# Microcontroller.net
KiCad netlist of a schematic drawn in Altium Designer
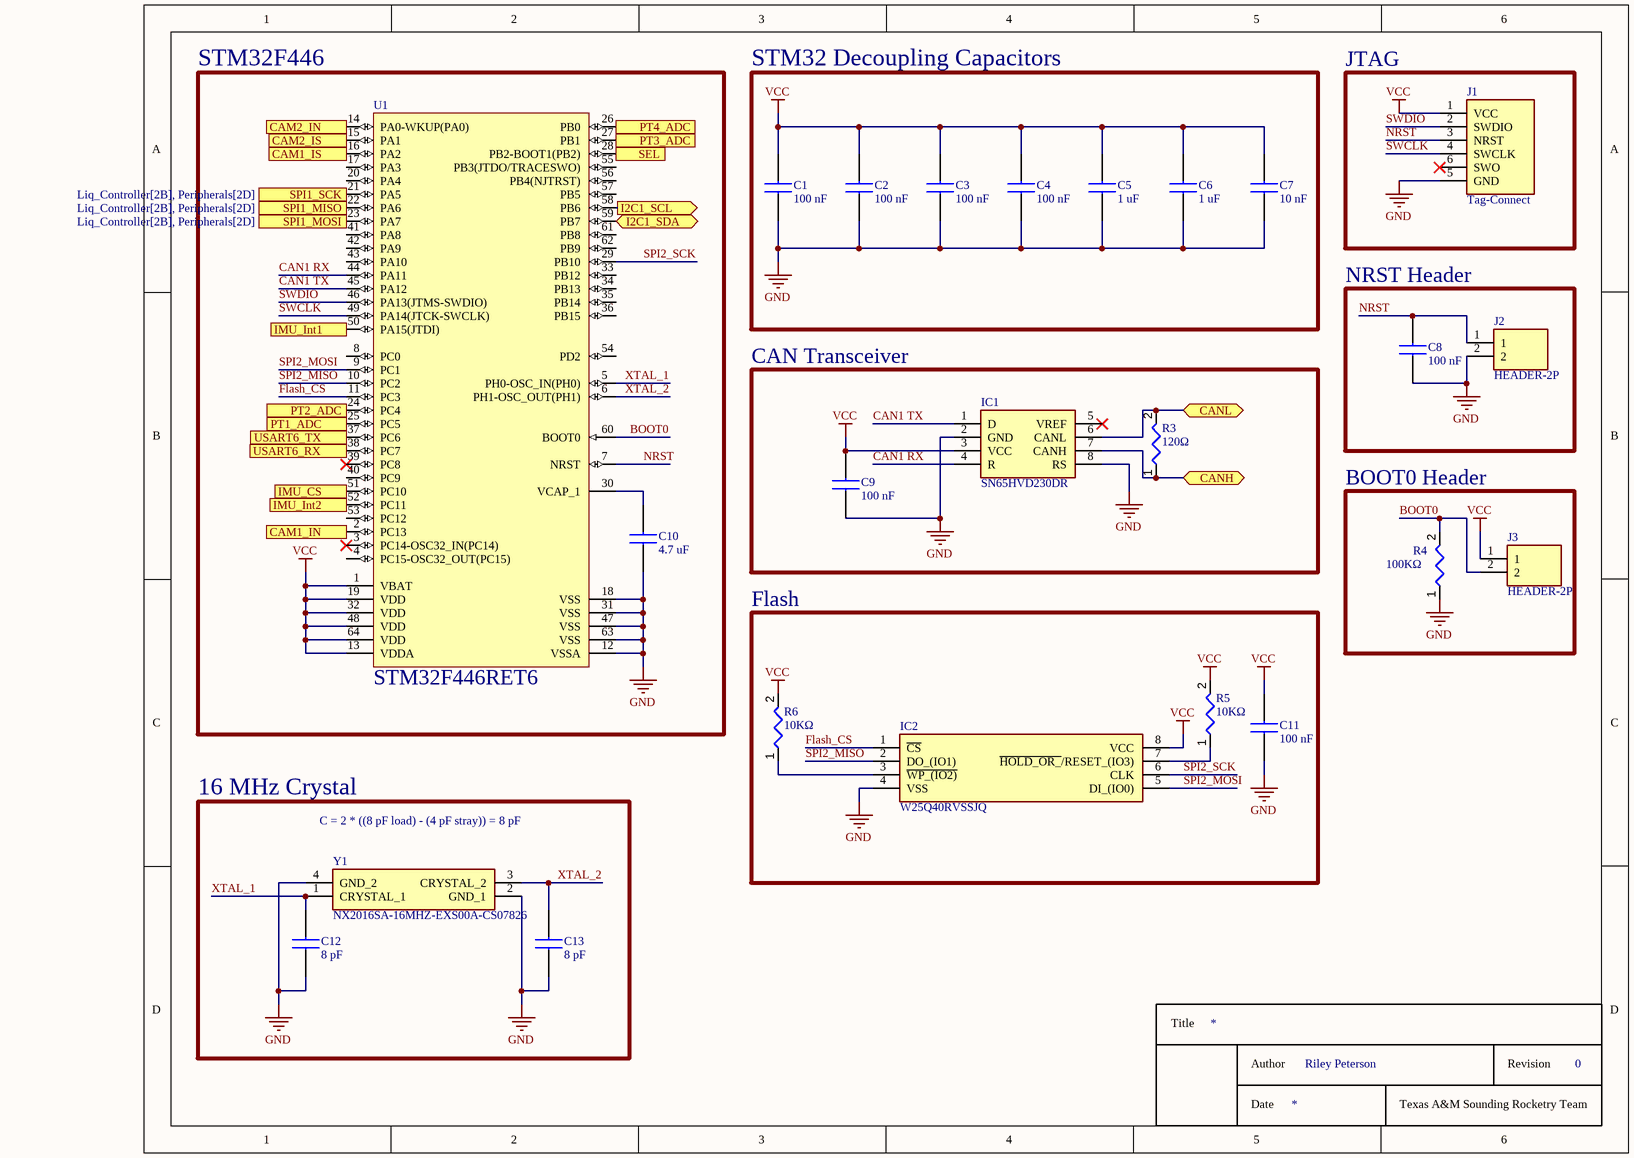
[diagram p0: Microcontroller.SchDoc]

(export (version "E")
  (design (tool "Eeschema 10.0.6"))
  (components
    (comp (ref "C1")
      (value "100 nF")
      (footprint "CAP_0603")
      (fields (field (name "TOLERANCE") "5%") (field (name "VOLTAGE") "50 V"))
      (libsource (lib "Capacitors") (part "Capacitor_BASE"))
    )
    (comp (ref "C2")
      (value "100 nF")
      (footprint "CAP_0603")
      (fields (field (name "TOLERANCE") "5%") (field (name "VOLTAGE") "50 V"))
      (libsource (lib "Capacitors") (part "Capacitor_BASE"))
    )
    (comp (ref "C3")
      (value "100 nF")
      (footprint "CAP_0603")
      (fields (field (name "TOLERANCE") "5%") (field (name "VOLTAGE") "50 V"))
      (libsource (lib "Capacitors") (part "Capacitor_BASE"))
    )
    (comp (ref "C4")
      (value "100 nF")
      (footprint "CAP_0603")
      (fields (field (name "TOLERANCE") "5%") (field (name "VOLTAGE") "50 V"))
      (libsource (lib "Capacitors") (part "Capacitor_BASE"))
    )
    (comp (ref "C5")
      (value "1 uF")
      (footprint "CAP_0603")
      (fields (field (name "TOLERANCE") "10%") (field (name "VOLTAGE") "25 V"))
      (libsource (lib "Capacitors") (part "Capacitor_BASE"))
    )
    (comp (ref "C6")
      (value "1 uF")
      (footprint "CAP_0603")
      (fields (field (name "TOLERANCE") "10%") (field (name "VOLTAGE") "25 V"))
      (libsource (lib "Capacitors") (part "Capacitor_BASE"))
    )
    (comp (ref "C7")
      (value "10 nF")
      (footprint "CAP_0603")
      (fields (field (name "TOLERANCE") "5%") (field (name "VOLTAGE") "50 V"))
      (libsource (lib "Capacitors") (part "Capacitor_BASE"))
    )
    (comp (ref "C8")
      (value "100 nF")
      (footprint "CAP_0603")
      (fields (field (name "TOLERANCE") "5%") (field (name "VOLTAGE") "50 V"))
      (libsource (lib "Capacitors") (part "Capacitor_BASE"))
    )
    (comp (ref "C9")
      (value "100 nF")
      (footprint "CAP_0603")
      (fields (field (name "TOLERANCE") "5%") (field (name "VOLTAGE") "50 V"))
      (libsource (lib "Capacitors") (part "Capacitor_BASE"))
    )
    (comp (ref "C10")
      (value "4.7 uF")
      (footprint "CAP_0603")
      (fields (field (name "TOLERANCE") "10%") (field (name "VOLTAGE") "25 V"))
      (libsource (lib "Capacitors") (part "Capacitor_BASE"))
    )
    (comp (ref "C11")
      (value "100 nF")
      (footprint "CAP_0603")
      (fields
        (field (name "TOLERANCE") "5%")
        (field (name "VOLTAGE") "50 V")
        (field (name "MPN") "581-06035C104JAT2A")
      )
      (libsource (lib "Capacitors") (part "Capacitor_BASE"))
    )
    (comp (ref "C12")
      (value "8 pF")
      (footprint "CAP_0603")
      (description "Multilayer Ceramic Capacitors MLCC - SMD/SMT 50V 8pF C0G 0603 5%")
      (fields (field (name "TOLERANCE") "5%") (field (name "VOLTAGE") "50 V"))
      (libsource (lib "Capacitors") (part "Capacitor_BASE"))
    )
    (comp (ref "C13")
      (value "8 pF")
      (footprint "CAP_0603")
      (description "Multilayer Ceramic Capacitors MLCC - SMD/SMT 50V 8pF C0G 0603 5%")
      (fields (field (name "TOLERANCE") "5%") (field (name "VOLTAGE") "50 V"))
      (libsource (lib "Capacitors") (part "Capacitor_BASE"))
    )
    (comp (ref "IC1")
      (value "SN65HVD230DR")
      (footprint "Miscellaneous:SOT127P600X175-8N")
      (description "CAN Transceiver")
      (fields (field (name "MOUSER PART NUMBER") "595-SN65HVD230DR"))
      (libsource (lib "Miscellaneous") (part "SN65HVD230DR"))
    )
    (comp (ref "IC2")
      (value "W25Q40RVSSJQ")
      (footprint "Miscellaneous:SOIC127P790X216-8N")
      (description "4 Mbit NOR Flash")
      (fields (field (name "MPN") "454-W25Q40RVSSJQ"))
      (libsource (lib "Miscellaneous") (part "W25Q40RVSSJQ"))
    )
    (comp (ref "J1")
      (value "Tag-Connect")
      (footprint "Connectors:TC2030-MCP")
      (description "Tag-Connect Programming Connector")
      (libsource (lib "Connectors") (part "Tag-Connect"))
    )
    (comp (ref "J2")
      (value "HEADER-2P")
      (footprint "Connectors:HDRV2W110P0X254_1X2_508X254X854P")
      (description "Connector\r\n61300211121")
      (fields
        (field (name "MANUFACTURER_PART_NUMBER") "61300211121")
        (field (name "MOUSER PART NUMBER") "710-61300211121")
      )
      (libsource (lib "Connectors") (part "HEADER-2P"))
    )
    (comp (ref "J3")
      (value "HEADER-2P")
      (footprint "Connectors:HDRV2W110P0X254_1X2_508X254X854P")
      (description "Connector\r\n61300211121")
      (fields
        (field (name "MANUFACTURER_PART_NUMBER") "61300211121")
        (field (name "MOUSER PART NUMBER") "710-61300211121")
      )
      (libsource (lib "Connectors") (part "HEADER-2P"))
    )
    (comp (ref "R3")
      (value "120Ω")
      (footprint "RES_0603")
      (description "Thick Film Resistors - SMD General Purpose Chip Resistor 0603, 120Ohms, 1%, 1/10W")
      (fields (field (name "TOLERANCE") "0.01") (field (name "POWER") "0.1W"))
      (libsource (lib "Resistors") (part "Resistor_BASE"))
    )
    (comp (ref "R4")
      (value "100KΩ")
      (footprint "RES_0603")
      (description "Thick Film Resistors - SMD General Purpose Chip Resistor 0603, 100kOhms, 1%, 1/10W")
      (fields (field (name "TOLERANCE") "0.01") (field (name "POWER") "0.1W"))
      (libsource (lib "Resistors") (part "Resistor_BASE"))
    )
    (comp (ref "R5")
      (value "10KΩ")
      (footprint "RES_0603")
      (description "Thick Film Resistors - SMD General Purpose Chip Resistor 0603, 10kOhms, 1%, 1/10W")
      (fields (field (name "TOLERANCE") "0.01") (field (name "POWER") "0.1W"))
      (libsource (lib "Resistors") (part "Resistor_BASE"))
    )
    (comp (ref "R6")
      (value "10KΩ")
      (footprint "RES_0603")
      (description "Thick Film Resistors - SMD General Purpose Chip Resistor 0603, 10kOhms, 1%, 1/10W")
      (fields (field (name "TOLERANCE") "0.01") (field (name "POWER") "0.1W"))
      (libsource (lib "Resistors") (part "Resistor_BASE"))
    )
    (comp (ref "U1")
      (value "STM32F446RET6")
      (footprint "Microcontrollers:QFP50P1200X1200X160-64N")
      (libsource (lib "Microcontrollers") (part "STM32F446RET6"))
    )
    (comp (ref "Y1")
      (value "NX2016SA-16MHZ-EXS00A-CS07826")
      (footprint "Crystals:NX2016SA16MHZEXS00ACS07826")
      (description "Crystal Oscillator")
      (fields (field (name "MOUSER PART NUMBER") "344-MHZEXS00ACS07826"))
      (libsource (lib "Crystals") (part "NX2016SA-16MHZ-EXS00A-CS07826"))
    )
  )
  (nets
    (net (code "1") (name "/BOOT0") (class "Default")
      (node (ref "J3") (pin "2") (pinfunction "2_2") (pintype "passive"))
      (node (ref "R4") (pin "2") (pinfunction "2_2") (pintype "passive"))
      (node (ref "U1") (pin "60") (pinfunction "BOOT0_60") (pintype "input"))
    )
    (net (code "2") (name "/CAM1_IN") (class "Default")
      (node (ref "U1") (pin "2") (pinfunction "PC13_2") (pintype "bidirectional"))
    )
    (net (code "3") (name "/CAM1_IS") (class "Default")
      (node (ref "U1") (pin "16") (pinfunction "PA2_16") (pintype "bidirectional"))
    )
    (net (code "4") (name "/CAM2_IN") (class "Default")
      (node (ref "U1") (pin "14") (pinfunction "PA0-WKUP(PA0)_14") (pintype "bidirectional"))
    )
    (net (code "5") (name "/CAM2_IS") (class "Default")
      (node (ref "U1") (pin "15") (pinfunction "PA1_15") (pintype "bidirectional"))
    )
    (net (code "6") (name "/CAN1 RX") (class "Default")
      (node (ref "IC1") (pin "4") (pinfunction "R_4") (pintype "passive"))
      (node (ref "U1") (pin "44") (pinfunction "PA11_44") (pintype "bidirectional"))
    )
    (net (code "7") (name "/CAN1 TX") (class "Default")
      (node (ref "IC1") (pin "1") (pinfunction "D_1") (pintype "passive"))
      (node (ref "U1") (pin "45") (pinfunction "PA12_45") (pintype "bidirectional"))
    )
    (net (code "8") (name "/CANH") (class "Default")
      (node (ref "IC1") (pin "7") (pinfunction "CANH_7") (pintype "passive"))
      (node (ref "R3") (pin "1") (pinfunction "1_1") (pintype "passive"))
    )
    (net (code "9") (name "/CANL") (class "Default")
      (node (ref "IC1") (pin "6") (pinfunction "CANL_6") (pintype "passive"))
      (node (ref "R3") (pin "2") (pinfunction "2_2") (pintype "passive"))
    )
    (net (code "10") (name "/Flash_CS") (class "Default")
      (node (ref "IC2") (pin "1") (pinfunction "~{CS}_1") (pintype "passive"))
      (node (ref "U1") (pin "11") (pinfunction "PC3_11") (pintype "bidirectional"))
    )
    (net (code "11") (name "/I2C1_SCL") (class "Default")
      (node (ref "U1") (pin "58") (pinfunction "PB6_58") (pintype "bidirectional"))
    )
    (net (code "12") (name "/I2C1_SDA") (class "Default")
      (node (ref "U1") (pin "59") (pinfunction "PB7_59") (pintype "bidirectional"))
    )
    (net (code "13") (name "/IMU_CS") (class "Default")
      (node (ref "U1") (pin "51") (pinfunction "PC10_51") (pintype "bidirectional"))
    )
    (net (code "14") (name "/IMU_Int1") (class "Default")
      (node (ref "U1") (pin "50") (pinfunction "PA15(JTDI)_50") (pintype "bidirectional"))
    )
    (net (code "15") (name "/IMU_Int2") (class "Default")
      (node (ref "U1") (pin "52") (pinfunction "PC11_52") (pintype "bidirectional"))
    )
    (net (code "16") (name "/NRST") (class "Default")
      (node (ref "C8") (pin "2") (pinfunction "2_2") (pintype "passive"))
      (node (ref "J1") (pin "3") (pinfunction "NRST_3") (pintype "passive"))
      (node (ref "J2") (pin "1") (pinfunction "1_1") (pintype "passive"))
      (node (ref "U1") (pin "7") (pinfunction "NRST_7") (pintype "bidirectional"))
    )
    (net (code "17") (name "/PT1_ADC") (class "Default")
      (node (ref "U1") (pin "25") (pinfunction "PC5_25") (pintype "bidirectional"))
    )
    (net (code "18") (name "/PT2_ADC") (class "Default")
      (node (ref "U1") (pin "24") (pinfunction "PC4_24") (pintype "bidirectional"))
    )
    (net (code "19") (name "/PT3_ADC") (class "Default")
      (node (ref "U1") (pin "27") (pinfunction "PB1_27") (pintype "bidirectional"))
    )
    (net (code "20") (name "/PT4_ADC") (class "Default")
      (node (ref "U1") (pin "26") (pinfunction "PB0_26") (pintype "bidirectional"))
    )
    (net (code "21") (name "/SEL") (class "Default")
      (node (ref "U1") (pin "28") (pinfunction "PB2-BOOT1(PB2)_28") (pintype "bidirectional"))
    )
    (net (code "22") (name "/SPI1_MISO") (class "Default")
      (node (ref "U1") (pin "22") (pinfunction "PA6_22") (pintype "bidirectional"))
    )
    (net (code "23") (name "/SPI1_MOSI") (class "Default")
      (node (ref "U1") (pin "23") (pinfunction "PA7_23") (pintype "bidirectional"))
    )
    (net (code "24") (name "/SPI1_SCK") (class "Default")
      (node (ref "U1") (pin "21") (pinfunction "PA5_21") (pintype "bidirectional"))
    )
    (net (code "25") (name "/SPI2_MISO") (class "Default")
      (node (ref "IC2") (pin "2") (pinfunction "DO_(IO1)_2") (pintype "passive"))
      (node (ref "U1") (pin "10") (pinfunction "PC2_10") (pintype "bidirectional"))
    )
    (net (code "26") (name "/SPI2_MOSI") (class "Default")
      (node (ref "IC2") (pin "5") (pinfunction "DI_(IO0)_5") (pintype "passive"))
      (node (ref "U1") (pin "9") (pinfunction "PC1_9") (pintype "bidirectional"))
    )
    (net (code "27") (name "/SPI2_SCK") (class "Default")
      (node (ref "IC2") (pin "6") (pinfunction "CLK_6") (pintype "passive"))
      (node (ref "U1") (pin "29") (pinfunction "PB10_29") (pintype "bidirectional"))
    )
    (net (code "28") (name "/SWCLK") (class "Default")
      (node (ref "J1") (pin "4") (pinfunction "SWCLK_4") (pintype "passive"))
      (node (ref "U1") (pin "49") (pinfunction "PA14(JTCK-SWCLK)_49") (pintype "bidirectional"))
    )
    (net (code "29") (name "/SWDIO") (class "Default")
      (node (ref "J1") (pin "2") (pinfunction "SWDIO_2") (pintype "passive"))
      (node (ref "U1") (pin "46") (pinfunction "PA13(JTMS-SWDIO)_46") (pintype "bidirectional"))
    )
    (net (code "30") (name "/USART6_RX") (class "Default")
      (node (ref "U1") (pin "38") (pinfunction "PC7_38") (pintype "bidirectional"))
    )
    (net (code "31") (name "/USART6_TX") (class "Default")
      (node (ref "U1") (pin "37") (pinfunction "PC6_37") (pintype "bidirectional"))
    )
    (net (code "32") (name "/XTAL_1") (class "Default")
      (node (ref "C12") (pin "2") (pinfunction "2_2") (pintype "passive"))
      (node (ref "U1") (pin "5") (pinfunction "PH0-OSC_IN(PH0)_5") (pintype "bidirectional"))
      (node (ref "Y1") (pin "1") (pinfunction "CRYSTAL_1_1") (pintype "passive"))
    )
    (net (code "33") (name "/XTAL_2") (class "Default")
      (node (ref "C13") (pin "2") (pinfunction "2_2") (pintype "passive"))
      (node (ref "U1") (pin "6") (pinfunction "PH1-OSC_OUT(PH1)_6") (pintype "bidirectional"))
      (node (ref "Y1") (pin "3") (pinfunction "CRYSTAL_2_3") (pintype "passive"))
    )
    (net (code "34") (name "GND") (class "Default")
      (node (ref "C1") (pin "1") (pinfunction "1_1") (pintype "passive"))
      (node (ref "C10") (pin "2") (pinfunction "2_2") (pintype "passive"))
      (node (ref "C11") (pin "1") (pinfunction "1_1") (pintype "passive"))
      (node (ref "C12") (pin "1") (pinfunction "1_1") (pintype "passive"))
      (node (ref "C13") (pin "1") (pinfunction "1_1") (pintype "passive"))
      (node (ref "C2") (pin "1") (pinfunction "1_1") (pintype "passive"))
      (node (ref "C3") (pin "1") (pinfunction "1_1") (pintype "passive"))
      (node (ref "C4") (pin "1") (pinfunction "1_1") (pintype "passive"))
      (node (ref "C5") (pin "1") (pinfunction "1_1") (pintype "passive"))
      (node (ref "C6") (pin "1") (pinfunction "1_1") (pintype "passive"))
      (node (ref "C7") (pin "2") (pinfunction "2_2") (pintype "passive"))
      (node (ref "C8") (pin "1") (pinfunction "1_1") (pintype "passive"))
      (node (ref "C9") (pin "1") (pinfunction "1_1") (pintype "passive"))
      (node (ref "IC1") (pin "2") (pinfunction "GND_2") (pintype "passive"))
      (node (ref "IC1") (pin "8") (pinfunction "RS_8") (pintype "passive"))
      (node (ref "IC2") (pin "4") (pinfunction "VSS_4") (pintype "passive"))
      (node (ref "J1") (pin "5") (pinfunction "GND_5") (pintype "passive"))
      (node (ref "J2") (pin "2") (pinfunction "2_2") (pintype "passive"))
      (node (ref "R4") (pin "1") (pinfunction "1_1") (pintype "passive"))
      (node (ref "U1") (pin "12") (pinfunction "VSSA_12") (pintype "power_in"))
      (node (ref "U1") (pin "18") (pinfunction "VSS_18") (pintype "power_in"))
      (node (ref "U1") (pin "31") (pinfunction "VSS_31") (pintype "power_in"))
      (node (ref "U1") (pin "47") (pinfunction "VSS_47") (pintype "power_in"))
      (node (ref "U1") (pin "63") (pinfunction "VSS_63") (pintype "power_in"))
      (node (ref "Y1") (pin "2") (pinfunction "GND_1_2") (pintype "passive"))
      (node (ref "Y1") (pin "4") (pinfunction "GND_2_4") (pintype "passive"))
    )
    (net (code "35") (name "Net-(IC2-~{HOLD_OR_}{slash}RESET_(IO3))") (class "Default")
      (node (ref "IC2") (pin "7") (pinfunction "~{HOLD_OR_}/RESET_(IO3)_7") (pintype "passive"))
      (node (ref "R5") (pin "1") (pinfunction "1_1") (pintype "passive"))
    )
    (net (code "36") (name "Net-(IC2-~{WP_(IO2)})") (class "Default")
      (node (ref "IC2") (pin "3") (pinfunction "~{WP_(IO2)}_3") (pintype "passive"))
      (node (ref "R6") (pin "1") (pinfunction "1_1") (pintype "passive"))
    )
    (net (code "37") (name "Net-(U1-VCAP_1)") (class "Default")
      (node (ref "C10") (pin "1") (pinfunction "1_1") (pintype "passive"))
      (node (ref "U1") (pin "30") (pinfunction "VCAP_1_30") (pintype "passive"))
    )
    (net (code "38") (name "VCC") (class "Default")
      (node (ref "C1") (pin "2") (pinfunction "2_2") (pintype "passive"))
      (node (ref "C11") (pin "2") (pinfunction "2_2") (pintype "passive"))
      (node (ref "C2") (pin "2") (pinfunction "2_2") (pintype "passive"))
      (node (ref "C3") (pin "2") (pinfunction "2_2") (pintype "passive"))
      (node (ref "C4") (pin "2") (pinfunction "2_2") (pintype "passive"))
      (node (ref "C5") (pin "2") (pinfunction "2_2") (pintype "passive"))
      (node (ref "C6") (pin "2") (pinfunction "2_2") (pintype "passive"))
      (node (ref "C7") (pin "1") (pinfunction "1_1") (pintype "passive"))
      (node (ref "C9") (pin "2") (pinfunction "2_2") (pintype "passive"))
      (node (ref "IC1") (pin "3") (pinfunction "VCC_3") (pintype "passive"))
      (node (ref "IC2") (pin "8") (pinfunction "VCC_8") (pintype "passive"))
      (node (ref "J1") (pin "1") (pinfunction "VCC_1") (pintype "passive"))
      (node (ref "J3") (pin "1") (pinfunction "1_1") (pintype "passive"))
      (node (ref "R5") (pin "2") (pinfunction "2_2") (pintype "passive"))
      (node (ref "R6") (pin "2") (pinfunction "2_2") (pintype "passive"))
      (node (ref "U1") (pin "1") (pinfunction "VBAT_1") (pintype "power_in"))
      (node (ref "U1") (pin "13") (pinfunction "VDDA_13") (pintype "power_in"))
      (node (ref "U1") (pin "19") (pinfunction "VDD_19") (pintype "power_in"))
      (node (ref "U1") (pin "32") (pinfunction "VDD_32") (pintype "power_in"))
      (node (ref "U1") (pin "48") (pinfunction "VDD_48") (pintype "power_in"))
      (node (ref "U1") (pin "64") (pinfunction "VDD_64") (pintype "power_in"))
    )
    (net (code "39") (name "unconnected-(IC1-VREF-Pad5)") (class "Default")
      (node (ref "IC1") (pin "5") (pinfunction "VREF_5") (pintype "passive+no_connect"))
    )
    (net (code "40") (name "unconnected-(J1-SWO-Pad6)") (class "Default")
      (node (ref "J1") (pin "6") (pinfunction "SWO_6") (pintype "passive+no_connect"))
    )
    (net (code "41") (name "unconnected-(U1-PA3-Pad17)") (class "Default")
      (node (ref "U1") (pin "17") (pinfunction "PA3_17") (pintype "bidirectional"))
    )
    (net (code "42") (name "unconnected-(U1-PA4-Pad20)") (class "Default")
      (node (ref "U1") (pin "20") (pinfunction "PA4_20") (pintype "bidirectional"))
    )
    (net (code "43") (name "unconnected-(U1-PA8-Pad41)") (class "Default")
      (node (ref "U1") (pin "41") (pinfunction "PA8_41") (pintype "bidirectional"))
    )
    (net (code "44") (name "unconnected-(U1-PA9-Pad42)") (class "Default")
      (node (ref "U1") (pin "42") (pinfunction "PA9_42") (pintype "bidirectional"))
    )
    (net (code "45") (name "unconnected-(U1-PA10-Pad43)") (class "Default")
      (node (ref "U1") (pin "43") (pinfunction "PA10_43") (pintype "bidirectional"))
    )
    (net (code "46") (name "unconnected-(U1-PB3(JTDO{slash}TRACESWO)-Pad55)") (class "Default")
      (node (ref "U1") (pin "55") (pinfunction "PB3(JTDO/TRACESWO)_55") (pintype "bidirectional"))
    )
    (net (code "47") (name "unconnected-(U1-PB4(NJTRST)-Pad56)") (class "Default")
      (node (ref "U1") (pin "56") (pinfunction "PB4(NJTRST)_56") (pintype "bidirectional"))
    )
    (net (code "48") (name "unconnected-(U1-PB5-Pad57)") (class "Default")
      (node (ref "U1") (pin "57") (pinfunction "PB5_57") (pintype "bidirectional"))
    )
    (net (code "49") (name "unconnected-(U1-PB8-Pad61)") (class "Default")
      (node (ref "U1") (pin "61") (pinfunction "PB8_61") (pintype "bidirectional"))
    )
    (net (code "50") (name "unconnected-(U1-PB9-Pad62)") (class "Default")
      (node (ref "U1") (pin "62") (pinfunction "PB9_62") (pintype "bidirectional"))
    )
    (net (code "51") (name "unconnected-(U1-PB12-Pad33)") (class "Default")
      (node (ref "U1") (pin "33") (pinfunction "PB12_33") (pintype "bidirectional"))
    )
    (net (code "52") (name "unconnected-(U1-PB13-Pad34)") (class "Default")
      (node (ref "U1") (pin "34") (pinfunction "PB13_34") (pintype "bidirectional"))
    )
    (net (code "53") (name "unconnected-(U1-PB14-Pad35)") (class "Default")
      (node (ref "U1") (pin "35") (pinfunction "PB14_35") (pintype "bidirectional"))
    )
    (net (code "54") (name "unconnected-(U1-PB15-Pad36)") (class "Default")
      (node (ref "U1") (pin "36") (pinfunction "PB15_36") (pintype "bidirectional"))
    )
    (net (code "55") (name "unconnected-(U1-PC0-Pad8)") (class "Default")
      (node (ref "U1") (pin "8") (pinfunction "PC0_8") (pintype "bidirectional"))
    )
    (net (code "56") (name "unconnected-(U1-PC8-Pad39)") (class "Default")
      (node (ref "U1") (pin "39") (pinfunction "PC8_39") (pintype "bidirectional+no_connect"))
    )
    (net (code "57") (name "unconnected-(U1-PC9-Pad40)") (class "Default")
      (node (ref "U1") (pin "40") (pinfunction "PC9_40") (pintype "bidirectional"))
    )
    (net (code "58") (name "unconnected-(U1-PC12-Pad53)") (class "Default")
      (node (ref "U1") (pin "53") (pinfunction "PC12_53") (pintype "bidirectional"))
    )
    (net (code "59") (name "unconnected-(U1-PC14-OSC32_IN(PC14)-Pad3)") (class "Default")
      (node (ref "U1") (pin "3") (pinfunction "PC14-OSC32_IN(PC14)_3") (pintype "bidirectional+no_connect"))
    )
    (net (code "60") (name "unconnected-(U1-PC15-OSC32_OUT(PC15)-Pad4)") (class "Default")
      (node (ref "U1") (pin "4") (pinfunction "PC15-OSC32_OUT(PC15)_4") (pintype "bidirectional"))
    )
    (net (code "61") (name "unconnected-(U1-PD2-Pad54)") (class "Default")
      (node (ref "U1") (pin "54") (pinfunction "PD2_54") (pintype "bidirectional"))
    )
  )
)
